# Hex_shield.net
KiCad netlist of a schematic drawn in EAGLE
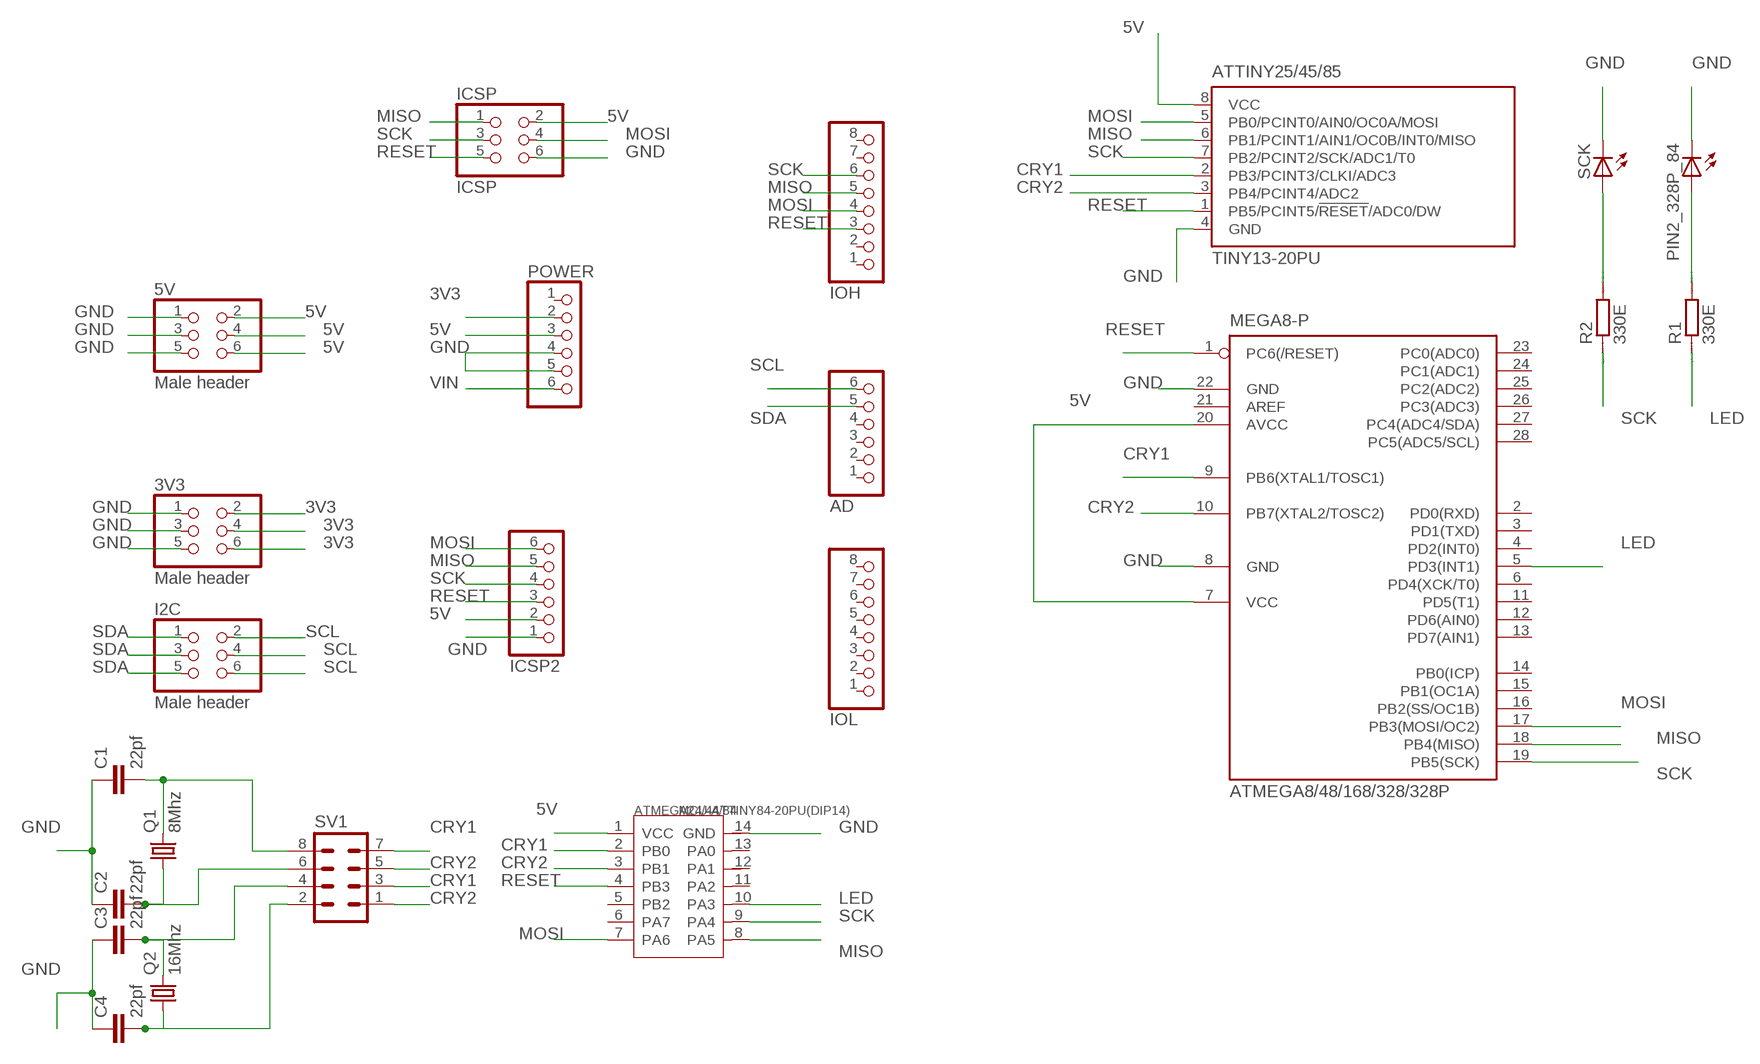
[diagram p0: schematic, sheet 1]

(export (version "E")
  (design (tool "Eeschema 10.0.6"))
  (components
    (comp (ref "3V3")
      (value "Male header")
      (footprint "eagle-import:2X03")
      (libsource (lib "eagle-import") (part "PINHD-2X3"))
    )
    (comp (ref "5V")
      (value "Male header")
      (footprint "eagle-import:2X03")
      (libsource (lib "eagle-import") (part "PINHD-2X3"))
    )
    (comp (ref "AD")
      (value "PINHD-1X6")
      (footprint "eagle-import:1X06")
      (libsource (lib "eagle-import") (part "PINHD-1X6"))
    )
    (comp (ref "ATMEGA8/48/168/328/328P")
      (value "MEGA8-P")
      (footprint "eagle-import:DIL28-3")
      (libsource (lib "eagle-import") (part "MEGA8-P"))
    )
    (comp (ref "ATMEGA24/44/84")
      (value "MCU-ATTINY84-20PU(DIP14)")
      (footprint "eagle-import:DIP14-2.54-17.24X6.35MM")
      (fields (field (name "MF") "Microchip") (field (name "MP") "ATTINY84-20PU"))
      (libsource (lib "eagle-import") (part "MCU-ATTINY84-20PU(DIP14)"))
    )
    (comp (ref "ATTINY25/45/85")
      (value "TINY13-20PU")
      (footprint "eagle-import:DIL08")
      (fields (field (name "MPN") "ATTINY13-20PU"))
      (libsource (lib "eagle-import") (part "TINY13PU-20"))
    )
    (comp (ref "C1")
      (value "22pf")
      (footprint "eagle-import:C2.5-2")
      (libsource (lib "eagle-import") (part "C2.5/2"))
    )
    (comp (ref "C2")
      (value "22pf")
      (footprint "eagle-import:C2.5-2")
      (libsource (lib "eagle-import") (part "C2.5/2"))
    )
    (comp (ref "C3")
      (value "22pf")
      (footprint "eagle-import:C2.5-2")
      (libsource (lib "eagle-import") (part "C2.5/2"))
    )
    (comp (ref "C4")
      (value "22pf")
      (footprint "eagle-import:C2.5-2")
      (libsource (lib "eagle-import") (part "C2.5/2"))
    )
    (comp (ref "I2C")
      (value "Male header")
      (footprint "eagle-import:2X03")
      (libsource (lib "eagle-import") (part "PINHD-2X3"))
    )
    (comp (ref "ICSP")
      (value "ICSP")
      (footprint "eagle-import:2X03")
      (libsource (lib "eagle-import") (part "PINHD-2X3"))
    )
    (comp (ref "ICSP2")
      (value "PINHD-1X6")
      (footprint "eagle-import:1X06")
      (libsource (lib "eagle-import") (part "PINHD-1X6"))
    )
    (comp (ref "IOH")
      (value "PINHD-1X8")
      (footprint "eagle-import:1X08")
      (libsource (lib "eagle-import") (part "PINHD-1X8"))
    )
    (comp (ref "IOL")
      (value "PINHD-1X8")
      (footprint "eagle-import:1X08")
      (libsource (lib "eagle-import") (part "PINHD-1X8"))
    )
    (comp (ref "PIN2_328P_84")
      (value "LED5MM")
      (footprint "eagle-import:LED5MM")
      (libsource (lib "eagle-import") (part "LED5MM"))
    )
    (comp (ref "POWER")
      (value "PINHD-1X6")
      (footprint "eagle-import:1X06")
      (libsource (lib "eagle-import") (part "PINHD-1X6"))
    )
    (comp (ref "Q1")
      (value "8Mhz")
      (footprint "eagle-import:HC49_S")
      (libsource (lib "eagle-import") (part "CRYSTALHC49S"))
    )
    (comp (ref "Q2")
      (value "16Mhz")
      (footprint "eagle-import:HC49_S")
      (libsource (lib "eagle-import") (part "CRYSTALHC49S"))
    )
    (comp (ref "R1")
      (value "330E")
      (footprint "eagle-import:0204_7")
      (libsource (lib "eagle-import") (part "R0204/7"))
    )
    (comp (ref "R2")
      (value "330E")
      (footprint "eagle-import:0204_7")
      (libsource (lib "eagle-import") (part "R0204/7"))
    )
    (comp (ref "SCK")
      (value "LED5MM")
      (footprint "eagle-import:LED5MM")
      (libsource (lib "eagle-import") (part "LED5MM"))
    )
    (comp (ref "SV1")
      (value "MA04-2")
      (footprint "eagle-import:MA04-2")
      (libsource (lib "eagle-import") (part "MA04-2"))
    )
  )
  (nets
    (net (code "1") (name "/3V3") (class "Default")
      (node (ref "3V3") (pin "2") (pinfunction "2_2") (pintype "passive"))
      (node (ref "3V3") (pin "4") (pinfunction "4_4") (pintype "passive"))
      (node (ref "3V3") (pin "6") (pinfunction "6_6") (pintype "passive"))
      (node (ref "POWER") (pin "2") (pinfunction "2_2") (pintype "passive"))
    )
    (net (code "2") (name "/5V") (class "Default")
      (node (ref "5V") (pin "2") (pinfunction "2_2") (pintype "passive"))
      (node (ref "5V") (pin "4") (pinfunction "4_4") (pintype "passive"))
      (node (ref "5V") (pin "6") (pinfunction "6_6") (pintype "passive"))
      (node (ref "ATMEGA24/44/84") (pin "1") (pinfunction "VCC_1") (pintype "bidirectional"))
      (node (ref "ATMEGA8/48/168/328/328P") (pin "20") (pinfunction "AVCC_20") (pintype "power_in"))
      (node (ref "ATMEGA8/48/168/328/328P") (pin "7") (pinfunction "VCC_7") (pintype "power_in"))
      (node (ref "ATTINY25/45/85") (pin "8") (pinfunction "VCC_8") (pintype "power_in"))
      (node (ref "ICSP") (pin "2") (pinfunction "2_2") (pintype "passive"))
      (node (ref "ICSP2") (pin "2") (pinfunction "2_2") (pintype "passive"))
      (node (ref "POWER") (pin "3") (pinfunction "3_3") (pintype "passive"))
    )
    (net (code "3") (name "/CRY1") (class "Default")
      (node (ref "ATMEGA24/44/84") (pin "2") (pinfunction "PB0_2") (pintype "bidirectional"))
      (node (ref "ATMEGA8/48/168/328/328P") (pin "9") (pinfunction "PB6(XTAL1/TOSC1)_9") (pintype "bidirectional"))
      (node (ref "ATTINY25/45/85") (pin "2") (pinfunction "PB3/PCINT3/CLKI/ADC3_2") (pintype "bidirectional"))
      (node (ref "SV1") (pin "3") (pinfunction "3_3") (pintype "passive"))
      (node (ref "SV1") (pin "7") (pinfunction "7_7") (pintype "passive"))
    )
    (net (code "4") (name "/CRY2") (class "Default")
      (node (ref "ATMEGA24/44/84") (pin "3") (pinfunction "PB1_3") (pintype "bidirectional"))
      (node (ref "ATMEGA8/48/168/328/328P") (pin "10") (pinfunction "PB7(XTAL2/TOSC2)_10") (pintype "bidirectional"))
      (node (ref "ATTINY25/45/85") (pin "3") (pinfunction "PB4/PCINT4/ADC2_3") (pintype "bidirectional"))
      (node (ref "SV1") (pin "1") (pinfunction "1_1") (pintype "passive"))
      (node (ref "SV1") (pin "5") (pinfunction "5_5") (pintype "passive"))
    )
    (net (code "5") (name "/GND") (class "Default")
      (node (ref "3V3") (pin "1") (pinfunction "1_1") (pintype "passive"))
      (node (ref "3V3") (pin "3") (pinfunction "3_3") (pintype "passive"))
      (node (ref "3V3") (pin "5") (pinfunction "5_5") (pintype "passive"))
      (node (ref "5V") (pin "1") (pinfunction "1_1") (pintype "passive"))
      (node (ref "5V") (pin "3") (pinfunction "3_3") (pintype "passive"))
      (node (ref "5V") (pin "5") (pinfunction "5_5") (pintype "passive"))
      (node (ref "ATMEGA24/44/84") (pin "14") (pinfunction "GND_14") (pintype "bidirectional"))
      (node (ref "ATMEGA8/48/168/328/328P") (pin "22") (pinfunction "GND_22") (pintype "power_in"))
      (node (ref "ATMEGA8/48/168/328/328P") (pin "8") (pinfunction "GND_8") (pintype "power_in"))
      (node (ref "ATTINY25/45/85") (pin "4") (pinfunction "GND_4") (pintype "power_in"))
      (node (ref "C1") (pin "1") (pinfunction "1_1") (pintype "passive"))
      (node (ref "C2") (pin "1") (pinfunction "1_1") (pintype "passive"))
      (node (ref "C3") (pin "1") (pinfunction "1_1") (pintype "passive"))
      (node (ref "C4") (pin "1") (pinfunction "1_1") (pintype "passive"))
      (node (ref "ICSP") (pin "6") (pinfunction "6_6") (pintype "passive"))
      (node (ref "ICSP2") (pin "1") (pinfunction "1_1") (pintype "passive"))
      (node (ref "PIN2_328P_84") (pin "K") (pinfunction "C_K") (pintype "passive"))
      (node (ref "POWER") (pin "4") (pinfunction "4_4") (pintype "passive"))
      (node (ref "POWER") (pin "5") (pinfunction "5_5") (pintype "passive"))
      (node (ref "SCK") (pin "K") (pinfunction "C_K") (pintype "passive"))
    )
    (net (code "6") (name "/LED") (class "Default")
      (node (ref "ATMEGA24/44/84") (pin "10") (pinfunction "PA3_10") (pintype "bidirectional"))
      (node (ref "ATMEGA8/48/168/328/328P") (pin "5") (pinfunction "PD3(INT1)_5") (pintype "bidirectional"))
      (node (ref "R1") (pin "1") (pinfunction "1_1") (pintype "passive"))
    )
    (net (code "7") (name "/MISO") (class "Default")
      (node (ref "ATMEGA24/44/84") (pin "8") (pinfunction "PA5_8") (pintype "bidirectional"))
      (node (ref "ATMEGA8/48/168/328/328P") (pin "18") (pinfunction "PB4(MISO)_18") (pintype "bidirectional"))
      (node (ref "ATTINY25/45/85") (pin "6") (pinfunction "PB1/PCINT1/AIN1/OC0B/INT0/MISO_6") (pintype "bidirectional"))
      (node (ref "ICSP") (pin "1") (pinfunction "1_1") (pintype "passive"))
      (node (ref "ICSP2") (pin "5") (pinfunction "5_5") (pintype "passive"))
      (node (ref "IOH") (pin "5") (pinfunction "5_5") (pintype "passive"))
    )
    (net (code "8") (name "/MOSI") (class "Default")
      (node (ref "ATMEGA24/44/84") (pin "7") (pinfunction "PA6_7") (pintype "bidirectional"))
      (node (ref "ATMEGA8/48/168/328/328P") (pin "17") (pinfunction "PB3(MOSI/OC2)_17") (pintype "bidirectional"))
      (node (ref "ATTINY25/45/85") (pin "5") (pinfunction "PB0/PCINT0/AIN0/OC0A/MOSI_5") (pintype "bidirectional"))
      (node (ref "ICSP") (pin "4") (pinfunction "4_4") (pintype "passive"))
      (node (ref "ICSP2") (pin "6") (pinfunction "6_6") (pintype "passive"))
      (node (ref "IOH") (pin "4") (pinfunction "4_4") (pintype "passive"))
    )
    (net (code "9") (name "/RESET") (class "Default")
      (node (ref "ATMEGA24/44/84") (pin "4") (pinfunction "PB3_4") (pintype "bidirectional"))
      (node (ref "ATMEGA8/48/168/328/328P") (pin "1") (pinfunction "PC6(/RESET)_1") (pintype "bidirectional"))
      (node (ref "ATTINY25/45/85") (pin "1") (pinfunction "PB5/PCINT5/~{RESET}/ADC0/DW_1") (pintype "bidirectional"))
      (node (ref "ICSP") (pin "5") (pinfunction "5_5") (pintype "passive"))
      (node (ref "ICSP2") (pin "3") (pinfunction "3_3") (pintype "passive"))
      (node (ref "IOH") (pin "3") (pinfunction "3_3") (pintype "passive"))
    )
    (net (code "10") (name "/SCK") (class "Default")
      (node (ref "ATMEGA24/44/84") (pin "9") (pinfunction "PA4_9") (pintype "bidirectional"))
      (node (ref "ATMEGA8/48/168/328/328P") (pin "19") (pinfunction "PB5(SCK)_19") (pintype "bidirectional"))
      (node (ref "ATTINY25/45/85") (pin "7") (pinfunction "PB2/PCINT2/SCK/ADC1/T0_7") (pintype "bidirectional"))
      (node (ref "ICSP") (pin "3") (pinfunction "3_3") (pintype "passive"))
      (node (ref "ICSP2") (pin "4") (pinfunction "4_4") (pintype "passive"))
      (node (ref "IOH") (pin "6") (pinfunction "6_6") (pintype "passive"))
      (node (ref "R2") (pin "1") (pinfunction "1_1") (pintype "passive"))
    )
    (net (code "11") (name "/SCL") (class "Default")
      (node (ref "AD") (pin "6") (pinfunction "6_6") (pintype "passive"))
      (node (ref "I2C") (pin "2") (pinfunction "2_2") (pintype "passive"))
      (node (ref "I2C") (pin "4") (pinfunction "4_4") (pintype "passive"))
      (node (ref "I2C") (pin "6") (pinfunction "6_6") (pintype "passive"))
    )
    (net (code "12") (name "/SDA") (class "Default")
      (node (ref "AD") (pin "5") (pinfunction "5_5") (pintype "passive"))
      (node (ref "I2C") (pin "1") (pinfunction "1_1") (pintype "passive"))
      (node (ref "I2C") (pin "3") (pinfunction "3_3") (pintype "passive"))
      (node (ref "I2C") (pin "5") (pinfunction "5_5") (pintype "passive"))
    )
    (net (code "13") (name "/VIN") (class "Default")
      (node (ref "POWER") (pin "6") (pinfunction "6_6") (pintype "passive"))
    )
    (net (code "14") (name "Net-(C1-Pad2)") (class "Default")
      (node (ref "C1") (pin "2") (pinfunction "2_2") (pintype "passive"))
      (node (ref "Q1") (pin "2") (pinfunction "2_2") (pintype "passive"))
      (node (ref "SV1") (pin "8") (pinfunction "8_8") (pintype "passive"))
    )
    (net (code "15") (name "Net-(C2-Pad2)") (class "Default")
      (node (ref "C2") (pin "2") (pinfunction "2_2") (pintype "passive"))
      (node (ref "Q1") (pin "1") (pinfunction "1_1") (pintype "passive"))
      (node (ref "SV1") (pin "6") (pinfunction "6_6") (pintype "passive"))
    )
    (net (code "16") (name "Net-(C3-Pad2)") (class "Default")
      (node (ref "C3") (pin "2") (pinfunction "2_2") (pintype "passive"))
      (node (ref "Q2") (pin "2") (pinfunction "2_2") (pintype "passive"))
      (node (ref "SV1") (pin "4") (pinfunction "4_4") (pintype "passive"))
    )
    (net (code "17") (name "Net-(C4-Pad2)") (class "Default")
      (node (ref "C4") (pin "2") (pinfunction "2_2") (pintype "passive"))
      (node (ref "Q2") (pin "1") (pinfunction "1_1") (pintype "passive"))
      (node (ref "SV1") (pin "2") (pinfunction "2_2") (pintype "passive"))
    )
    (net (code "18") (name "Net-(PIN2_328P_84-PadA)") (class "Default")
      (node (ref "PIN2_328P_84") (pin "A") (pinfunction "A_A") (pintype "passive"))
      (node (ref "R1") (pin "2") (pinfunction "2_2") (pintype "passive"))
    )
    (net (code "19") (name "Net-(R2-Pad2)") (class "Default")
      (node (ref "R2") (pin "2") (pinfunction "2_2") (pintype "passive"))
      (node (ref "SCK") (pin "A") (pinfunction "A_A") (pintype "passive"))
    )
    (net (code "20") (name "unconnected-(AD-Pad1)") (class "Default")
      (node (ref "AD") (pin "1") (pinfunction "1_1") (pintype "passive"))
    )
    (net (code "21") (name "unconnected-(AD-Pad2)") (class "Default")
      (node (ref "AD") (pin "2") (pinfunction "2_2") (pintype "passive"))
    )
    (net (code "22") (name "unconnected-(AD-Pad3)") (class "Default")
      (node (ref "AD") (pin "3") (pinfunction "3_3") (pintype "passive"))
    )
    (net (code "23") (name "unconnected-(AD-Pad4)") (class "Default")
      (node (ref "AD") (pin "4") (pinfunction "4_4") (pintype "passive"))
    )
    (net (code "24") (name "unconnected-(ATMEGA8/48/168/328/328P-AREF-Pad21)") (class "Default")
      (node (ref "ATMEGA8/48/168/328/328P") (pin "21") (pinfunction "AREF_21") (pintype "passive"))
    )
    (net (code "25") (name "unconnected-(ATMEGA8/48/168/328/328P-PB0(ICP)-Pad14)") (class "Default")
      (node (ref "ATMEGA8/48/168/328/328P") (pin "14") (pinfunction "PB0(ICP)_14") (pintype "bidirectional"))
    )
    (net (code "26") (name "unconnected-(ATMEGA8/48/168/328/328P-PB1(OC1A)-Pad15)") (class "Default")
      (node (ref "ATMEGA8/48/168/328/328P") (pin "15") (pinfunction "PB1(OC1A)_15") (pintype "bidirectional"))
    )
    (net (code "27") (name "unconnected-(ATMEGA8/48/168/328/328P-PB2(SS{slash}OC1B)-Pad16)") (class "Default")
      (node (ref "ATMEGA8/48/168/328/328P") (pin "16") (pinfunction "PB2(SS/OC1B)_16") (pintype "bidirectional"))
    )
    (net (code "28") (name "unconnected-(ATMEGA8/48/168/328/328P-PC0(ADC0)-Pad23)") (class "Default")
      (node (ref "ATMEGA8/48/168/328/328P") (pin "23") (pinfunction "PC0(ADC0)_23") (pintype "bidirectional"))
    )
    (net (code "29") (name "unconnected-(ATMEGA8/48/168/328/328P-PC1(ADC1)-Pad24)") (class "Default")
      (node (ref "ATMEGA8/48/168/328/328P") (pin "24") (pinfunction "PC1(ADC1)_24") (pintype "bidirectional"))
    )
    (net (code "30") (name "unconnected-(ATMEGA8/48/168/328/328P-PC2(ADC2)-Pad25)") (class "Default")
      (node (ref "ATMEGA8/48/168/328/328P") (pin "25") (pinfunction "PC2(ADC2)_25") (pintype "bidirectional"))
    )
    (net (code "31") (name "unconnected-(ATMEGA8/48/168/328/328P-PC3(ADC3)-Pad26)") (class "Default")
      (node (ref "ATMEGA8/48/168/328/328P") (pin "26") (pinfunction "PC3(ADC3)_26") (pintype "bidirectional"))
    )
    (net (code "32") (name "unconnected-(ATMEGA8/48/168/328/328P-PC4(ADC4{slash}SDA)-Pad27)") (class "Default")
      (node (ref "ATMEGA8/48/168/328/328P") (pin "27") (pinfunction "PC4(ADC4/SDA)_27") (pintype "bidirectional"))
    )
    (net (code "33") (name "unconnected-(ATMEGA8/48/168/328/328P-PC5(ADC5{slash}SCL)-Pad28)") (class "Default")
      (node (ref "ATMEGA8/48/168/328/328P") (pin "28") (pinfunction "PC5(ADC5/SCL)_28") (pintype "bidirectional"))
    )
    (net (code "34") (name "unconnected-(ATMEGA8/48/168/328/328P-PD0(RXD)-Pad2)") (class "Default")
      (node (ref "ATMEGA8/48/168/328/328P") (pin "2") (pinfunction "PD0(RXD)_2") (pintype "bidirectional"))
    )
    (net (code "35") (name "unconnected-(ATMEGA8/48/168/328/328P-PD1(TXD)-Pad3)") (class "Default")
      (node (ref "ATMEGA8/48/168/328/328P") (pin "3") (pinfunction "PD1(TXD)_3") (pintype "bidirectional"))
    )
    (net (code "36") (name "unconnected-(ATMEGA8/48/168/328/328P-PD2(INT0)-Pad4)") (class "Default")
      (node (ref "ATMEGA8/48/168/328/328P") (pin "4") (pinfunction "PD2(INT0)_4") (pintype "bidirectional"))
    )
    (net (code "37") (name "unconnected-(ATMEGA8/48/168/328/328P-PD4(XCK{slash}T0)-Pad6)") (class "Default")
      (node (ref "ATMEGA8/48/168/328/328P") (pin "6") (pinfunction "PD4(XCK/T0)_6") (pintype "bidirectional"))
    )
    (net (code "38") (name "unconnected-(ATMEGA8/48/168/328/328P-PD5(T1)-Pad11)") (class "Default")
      (node (ref "ATMEGA8/48/168/328/328P") (pin "11") (pinfunction "PD5(T1)_11") (pintype "bidirectional"))
    )
    (net (code "39") (name "unconnected-(ATMEGA8/48/168/328/328P-PD6(AIN0)-Pad12)") (class "Default")
      (node (ref "ATMEGA8/48/168/328/328P") (pin "12") (pinfunction "PD6(AIN0)_12") (pintype "bidirectional"))
    )
    (net (code "40") (name "unconnected-(ATMEGA8/48/168/328/328P-PD7(AIN1)-Pad13)") (class "Default")
      (node (ref "ATMEGA8/48/168/328/328P") (pin "13") (pinfunction "PD7(AIN1)_13") (pintype "bidirectional"))
    )
    (net (code "41") (name "unconnected-(ATMEGA24/44/84-PA0-Pad13)") (class "Default")
      (node (ref "ATMEGA24/44/84") (pin "13") (pinfunction "PA0_13") (pintype "bidirectional"))
    )
    (net (code "42") (name "unconnected-(ATMEGA24/44/84-PA1-Pad12)") (class "Default")
      (node (ref "ATMEGA24/44/84") (pin "12") (pinfunction "PA1_12") (pintype "bidirectional"))
    )
    (net (code "43") (name "unconnected-(ATMEGA24/44/84-PA2-Pad11)") (class "Default")
      (node (ref "ATMEGA24/44/84") (pin "11") (pinfunction "PA2_11") (pintype "bidirectional"))
    )
    (net (code "44") (name "unconnected-(ATMEGA24/44/84-PA7-Pad6)") (class "Default")
      (node (ref "ATMEGA24/44/84") (pin "6") (pinfunction "PA7_6") (pintype "bidirectional"))
    )
    (net (code "45") (name "unconnected-(ATMEGA24/44/84-PB2-Pad5)") (class "Default")
      (node (ref "ATMEGA24/44/84") (pin "5") (pinfunction "PB2_5") (pintype "bidirectional"))
    )
    (net (code "46") (name "unconnected-(IOH-Pad1)") (class "Default")
      (node (ref "IOH") (pin "1") (pinfunction "1_1") (pintype "passive"))
    )
    (net (code "47") (name "unconnected-(IOH-Pad2)") (class "Default")
      (node (ref "IOH") (pin "2") (pinfunction "2_2") (pintype "passive"))
    )
    (net (code "48") (name "unconnected-(IOH-Pad7)") (class "Default")
      (node (ref "IOH") (pin "7") (pinfunction "7_7") (pintype "passive"))
    )
    (net (code "49") (name "unconnected-(IOH-Pad8)") (class "Default")
      (node (ref "IOH") (pin "8") (pinfunction "8_8") (pintype "passive"))
    )
    (net (code "50") (name "unconnected-(IOL-Pad1)") (class "Default")
      (node (ref "IOL") (pin "1") (pinfunction "1_1") (pintype "passive"))
    )
    (net (code "51") (name "unconnected-(IOL-Pad2)") (class "Default")
      (node (ref "IOL") (pin "2") (pinfunction "2_2") (pintype "passive"))
    )
    (net (code "52") (name "unconnected-(IOL-Pad3)") (class "Default")
      (node (ref "IOL") (pin "3") (pinfunction "3_3") (pintype "passive"))
    )
    (net (code "53") (name "unconnected-(IOL-Pad4)") (class "Default")
      (node (ref "IOL") (pin "4") (pinfunction "4_4") (pintype "passive"))
    )
    (net (code "54") (name "unconnected-(IOL-Pad5)") (class "Default")
      (node (ref "IOL") (pin "5") (pinfunction "5_5") (pintype "passive"))
    )
    (net (code "55") (name "unconnected-(IOL-Pad6)") (class "Default")
      (node (ref "IOL") (pin "6") (pinfunction "6_6") (pintype "passive"))
    )
    (net (code "56") (name "unconnected-(IOL-Pad7)") (class "Default")
      (node (ref "IOL") (pin "7") (pinfunction "7_7") (pintype "passive"))
    )
    (net (code "57") (name "unconnected-(IOL-Pad8)") (class "Default")
      (node (ref "IOL") (pin "8") (pinfunction "8_8") (pintype "passive"))
    )
    (net (code "58") (name "unconnected-(POWER-Pad1)") (class "Default")
      (node (ref "POWER") (pin "1") (pinfunction "1_1") (pintype "passive"))
    )
  )
)
